# RPi-ILDA_v1.net
KiCad netlist of a schematic drawn in EAGLE
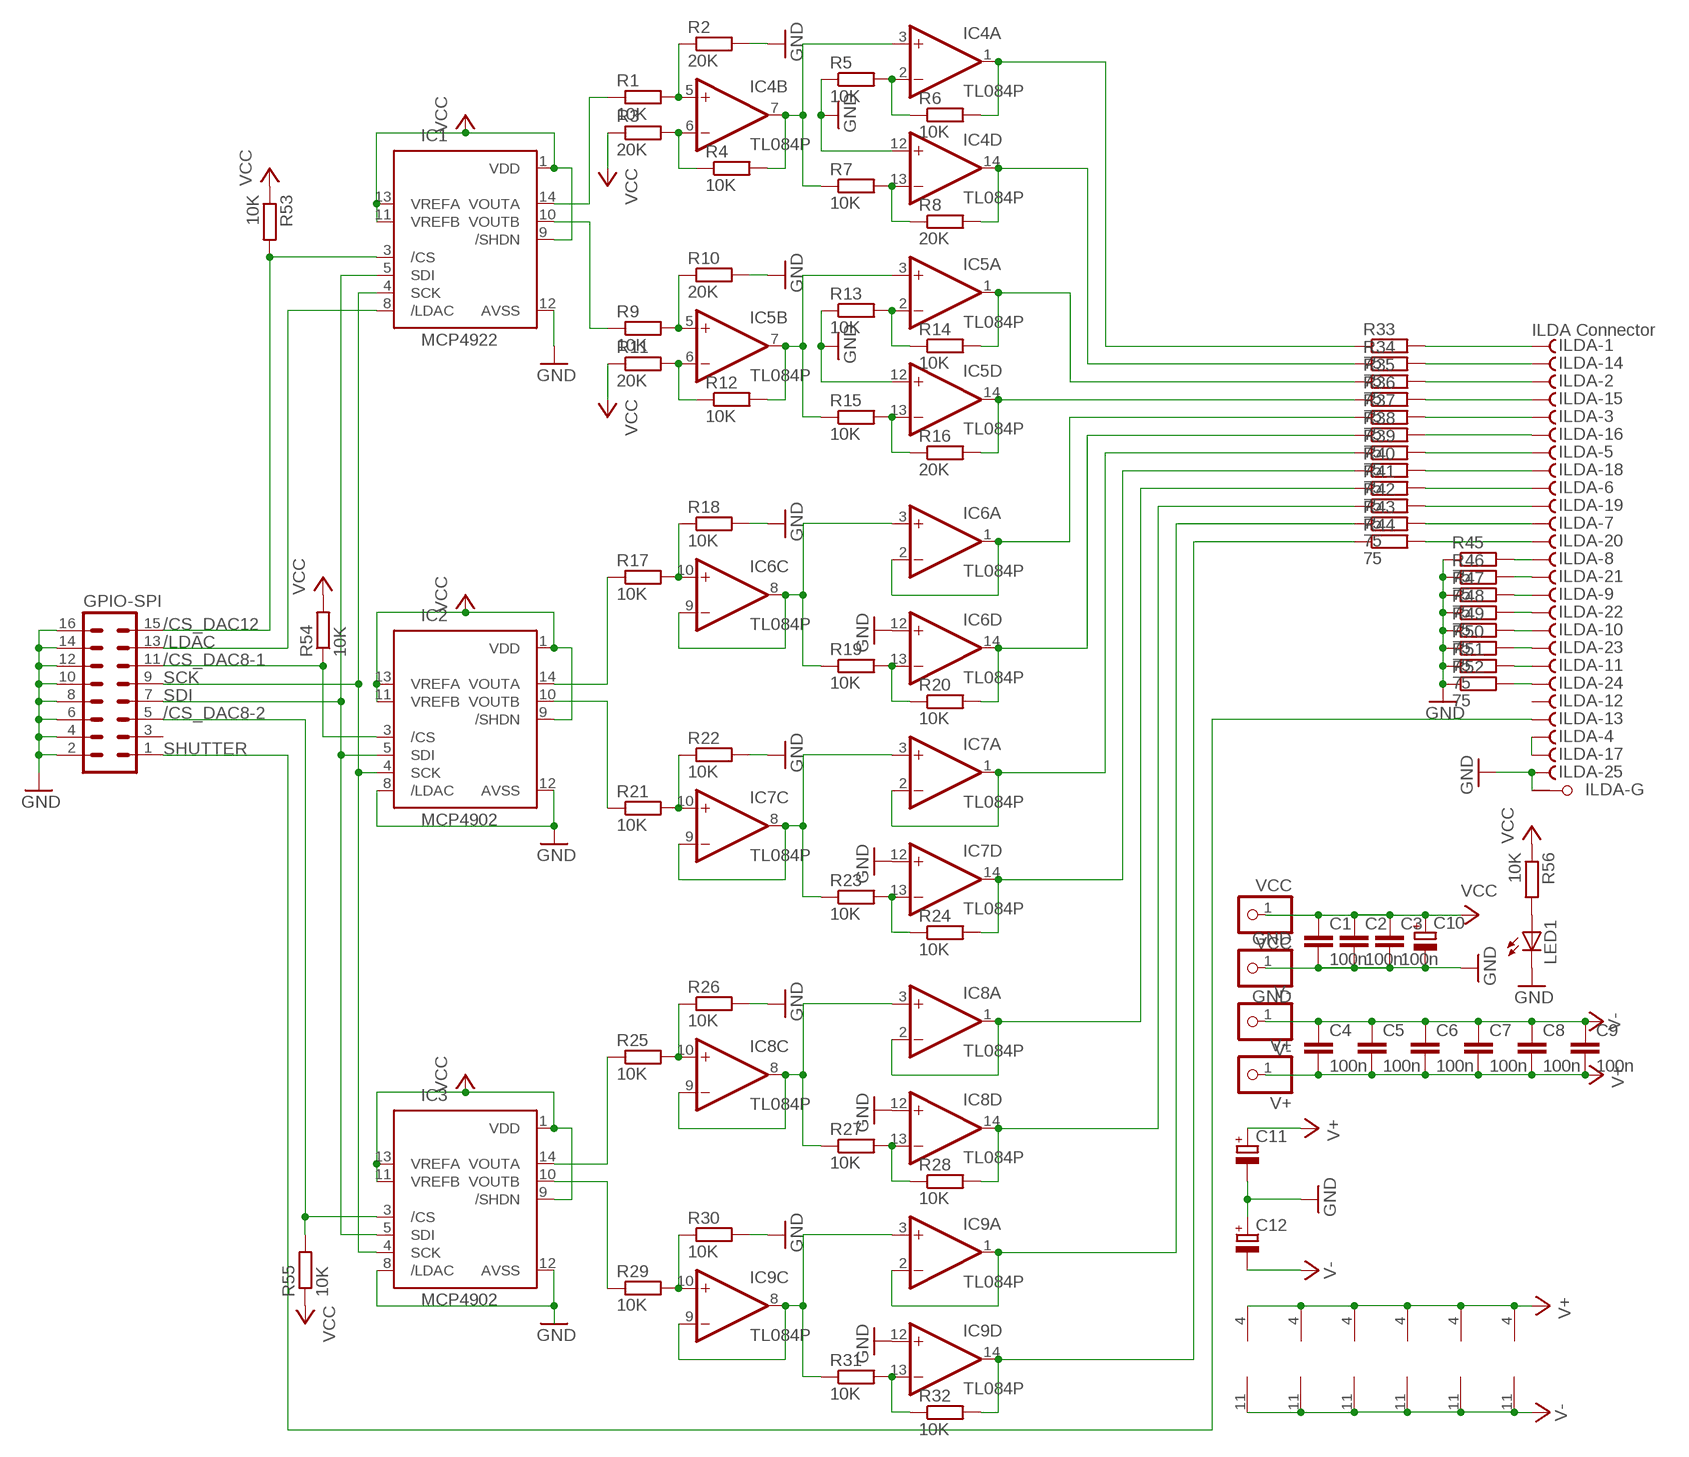
[diagram p0: schematic, sheet 1]

(export (version "E")
  (design (tool "Eeschema 10.0.6"))
  (components
    (comp (ref "C1")
      (value "100n")
      (footprint "eagle-import:C050-024X044")
      (libsource (lib "eagle-import") (part "C-EU050-024X044"))
    )
    (comp (ref "C2")
      (value "100n")
      (footprint "eagle-import:C050-024X044")
      (libsource (lib "eagle-import") (part "C-EU050-024X044"))
    )
    (comp (ref "C3")
      (value "100n")
      (footprint "eagle-import:C050-024X044")
      (libsource (lib "eagle-import") (part "C-EU050-024X044"))
    )
    (comp (ref "C4")
      (value "100n")
      (footprint "eagle-import:C050-024X044")
      (libsource (lib "eagle-import") (part "C-EU050-024X044"))
    )
    (comp (ref "C5")
      (value "100n")
      (footprint "eagle-import:C050-024X044")
      (libsource (lib "eagle-import") (part "C-EU050-024X044"))
    )
    (comp (ref "C6")
      (value "100n")
      (footprint "eagle-import:C050-024X044")
      (libsource (lib "eagle-import") (part "C-EU050-024X044"))
    )
    (comp (ref "C7")
      (value "100n")
      (footprint "eagle-import:C050-024X044")
      (libsource (lib "eagle-import") (part "C-EU050-024X044"))
    )
    (comp (ref "C8")
      (value "100n")
      (footprint "eagle-import:C050-024X044")
      (libsource (lib "eagle-import") (part "C-EU050-024X044"))
    )
    (comp (ref "C9")
      (value "100n")
      (footprint "eagle-import:C050-024X044")
      (libsource (lib "eagle-import") (part "C-EU050-024X044"))
    )
    (comp (ref "C10")
      (value "CPOL-EUE5-6")
      (footprint "eagle-import:E5-6")
      (libsource (lib "eagle-import") (part "CPOL-EUE5-6"))
    )
    (comp (ref "C11")
      (value "CPOL-EUE5-6")
      (footprint "eagle-import:E5-6")
      (libsource (lib "eagle-import") (part "CPOL-EUE5-6"))
    )
    (comp (ref "C12")
      (value "CPOL-EUE5-6")
      (footprint "eagle-import:E5-6")
      (libsource (lib "eagle-import") (part "CPOL-EUE5-6"))
    )
    (comp (ref "GND")
      (value "GND")
      (footprint "eagle-import:1X01")
      (libsource (lib "eagle-import") (part "PINHD-1X1"))
    )
    (comp (ref "GPIO-SPI")
      (value "MA08-2")
      (footprint "eagle-import:MA08-2")
      (libsource (lib "eagle-import") (part "MA08-2"))
    )
    (comp (ref "IC1")
      (value "MCP4922")
      (footprint "eagle-import:DIL14")
      (libsource (lib "eagle-import") (part "MCP4922"))
    )
    (comp (ref "IC2")
      (value "MCP4902")
      (footprint "eagle-import:DIL14")
      (libsource (lib "eagle-import") (part "MCP4922"))
    )
    (comp (ref "IC3")
      (value "MCP4902")
      (footprint "eagle-import:DIL14")
      (libsource (lib "eagle-import") (part "MCP4922"))
    )
    (comp (ref "IC4")
      (value "TL084P")
      (footprint "eagle-import:DIL14")
      (libsource (lib "eagle-import") (part "TL084P"))
    )
    (comp (ref "IC5")
      (value "TL084P")
      (footprint "eagle-import:DIL14")
      (libsource (lib "eagle-import") (part "TL084P"))
    )
    (comp (ref "IC6")
      (value "TL084P")
      (footprint "eagle-import:DIL14")
      (libsource (lib "eagle-import") (part "TL084P"))
    )
    (comp (ref "IC7")
      (value "TL084P")
      (footprint "eagle-import:DIL14")
      (libsource (lib "eagle-import") (part "TL084P"))
    )
    (comp (ref "IC8")
      (value "TL084P")
      (footprint "eagle-import:DIL14")
      (libsource (lib "eagle-import") (part "TL084P"))
    )
    (comp (ref "IC9")
      (value "TL084P")
      (footprint "eagle-import:DIL14")
      (libsource (lib "eagle-import") (part "TL084P"))
    )
    (comp (ref "ILDA")
      (value "ILDA Connector")
      (footprint "eagle-import:F25HP")
      (libsource (lib "eagle-import") (part "F25HPS"))
    )
    (comp (ref "LED1")
      (value "LED3MM")
      (footprint "eagle-import:LED3MM")
      (libsource (lib "eagle-import") (part "LED3MM"))
    )
    (comp (ref "R1")
      (value "10K")
      (footprint "eagle-import:0204_5")
      (libsource (lib "eagle-import") (part "R-EU_0204/5"))
    )
    (comp (ref "R2")
      (value "20K")
      (footprint "eagle-import:0204V")
      (libsource (lib "eagle-import") (part "R-EU_0204/2V"))
    )
    (comp (ref "R3")
      (value "20K")
      (footprint "eagle-import:0204_5")
      (libsource (lib "eagle-import") (part "R-EU_0204/5"))
    )
    (comp (ref "R4")
      (value "10K")
      (footprint "eagle-import:0204V")
      (libsource (lib "eagle-import") (part "R-EU_0204/2V"))
    )
    (comp (ref "R5")
      (value "10K")
      (footprint "eagle-import:0204V")
      (libsource (lib "eagle-import") (part "R-EU_0204/2V"))
    )
    (comp (ref "R6")
      (value "10K")
      (footprint "eagle-import:0204V")
      (libsource (lib "eagle-import") (part "R-EU_0204/2V"))
    )
    (comp (ref "R7")
      (value "10K")
      (footprint "eagle-import:0204_5")
      (libsource (lib "eagle-import") (part "R-EU_0204/5"))
    )
    (comp (ref "R8")
      (value "20K")
      (footprint "eagle-import:0204V")
      (libsource (lib "eagle-import") (part "R-EU_0204/2V"))
    )
    (comp (ref "R9")
      (value "10K")
      (footprint "eagle-import:0204_5")
      (libsource (lib "eagle-import") (part "R-EU_0204/5"))
    )
    (comp (ref "R10")
      (value "20K")
      (footprint "eagle-import:0204V")
      (libsource (lib "eagle-import") (part "R-EU_0204/2V"))
    )
    (comp (ref "R11")
      (value "20K")
      (footprint "eagle-import:0204_5")
      (libsource (lib "eagle-import") (part "R-EU_0204/5"))
    )
    (comp (ref "R12")
      (value "10K")
      (footprint "eagle-import:0204V")
      (libsource (lib "eagle-import") (part "R-EU_0204/2V"))
    )
    (comp (ref "R13")
      (value "10K")
      (footprint "eagle-import:0204V")
      (libsource (lib "eagle-import") (part "R-EU_0204/2V"))
    )
    (comp (ref "R14")
      (value "10K")
      (footprint "eagle-import:0204V")
      (libsource (lib "eagle-import") (part "R-EU_0204/2V"))
    )
    (comp (ref "R15")
      (value "10K")
      (footprint "eagle-import:0204_5")
      (libsource (lib "eagle-import") (part "R-EU_0204/5"))
    )
    (comp (ref "R16")
      (value "20K")
      (footprint "eagle-import:0204V")
      (libsource (lib "eagle-import") (part "R-EU_0204/2V"))
    )
    (comp (ref "R17")
      (value "10K")
      (footprint "eagle-import:0204_5")
      (libsource (lib "eagle-import") (part "R-EU_0204/5"))
    )
    (comp (ref "R18")
      (value "10K")
      (footprint "eagle-import:0204V")
      (libsource (lib "eagle-import") (part "R-EU_0204/2V"))
    )
    (comp (ref "R19")
      (value "10K")
      (footprint "eagle-import:0204V")
      (libsource (lib "eagle-import") (part "R-EU_0204/2V"))
    )
    (comp (ref "R20")
      (value "10K")
      (footprint "eagle-import:0204V")
      (libsource (lib "eagle-import") (part "R-EU_0204/2V"))
    )
    (comp (ref "R21")
      (value "10K")
      (footprint "eagle-import:0204_5")
      (libsource (lib "eagle-import") (part "R-EU_0204/5"))
    )
    (comp (ref "R22")
      (value "10K")
      (footprint "eagle-import:0204_5")
      (libsource (lib "eagle-import") (part "R-EU_0204/5"))
    )
    (comp (ref "R23")
      (value "10K")
      (footprint "eagle-import:0204V")
      (libsource (lib "eagle-import") (part "R-EU_0204/2V"))
    )
    (comp (ref "R24")
      (value "10K")
      (footprint "eagle-import:0204V")
      (libsource (lib "eagle-import") (part "R-EU_0204/2V"))
    )
    (comp (ref "R25")
      (value "10K")
      (footprint "eagle-import:0204_5")
      (libsource (lib "eagle-import") (part "R-EU_0204/5"))
    )
    (comp (ref "R26")
      (value "10K")
      (footprint "eagle-import:0204V")
      (libsource (lib "eagle-import") (part "R-EU_0204/2V"))
    )
    (comp (ref "R27")
      (value "10K")
      (footprint "eagle-import:0204V")
      (libsource (lib "eagle-import") (part "R-EU_0204/2V"))
    )
    (comp (ref "R28")
      (value "10K")
      (footprint "eagle-import:0204V")
      (libsource (lib "eagle-import") (part "R-EU_0204/2V"))
    )
    (comp (ref "R29")
      (value "10K")
      (footprint "eagle-import:0204_5")
      (libsource (lib "eagle-import") (part "R-EU_0204/5"))
    )
    (comp (ref "R30")
      (value "10K")
      (footprint "eagle-import:0204_5")
      (libsource (lib "eagle-import") (part "R-EU_0204/5"))
    )
    (comp (ref "R31")
      (value "10K")
      (footprint "eagle-import:0204V")
      (libsource (lib "eagle-import") (part "R-EU_0204/2V"))
    )
    (comp (ref "R32")
      (value "10K")
      (footprint "eagle-import:0204V")
      (libsource (lib "eagle-import") (part "R-EU_0204/2V"))
    )
    (comp (ref "R33")
      (value "75")
      (footprint "eagle-import:0204V")
      (libsource (lib "eagle-import") (part "R-EU_0204/2V"))
    )
    (comp (ref "R34")
      (value "75")
      (footprint "eagle-import:0204V")
      (libsource (lib "eagle-import") (part "R-EU_0204/2V"))
    )
    (comp (ref "R35")
      (value "75")
      (footprint "eagle-import:0204V")
      (libsource (lib "eagle-import") (part "R-EU_0204/2V"))
    )
    (comp (ref "R36")
      (value "75")
      (footprint "eagle-import:0204V")
      (libsource (lib "eagle-import") (part "R-EU_0204/2V"))
    )
    (comp (ref "R37")
      (value "75")
      (footprint "eagle-import:0204V")
      (libsource (lib "eagle-import") (part "R-EU_0204/2V"))
    )
    (comp (ref "R38")
      (value "75")
      (footprint "eagle-import:0204V")
      (libsource (lib "eagle-import") (part "R-EU_0204/2V"))
    )
    (comp (ref "R39")
      (value "75")
      (footprint "eagle-import:0204V")
      (libsource (lib "eagle-import") (part "R-EU_0204/2V"))
    )
    (comp (ref "R40")
      (value "75")
      (footprint "eagle-import:0204V")
      (libsource (lib "eagle-import") (part "R-EU_0204/2V"))
    )
    (comp (ref "R41")
      (value "75")
      (footprint "eagle-import:0204V")
      (libsource (lib "eagle-import") (part "R-EU_0204/2V"))
    )
    (comp (ref "R42")
      (value "75")
      (footprint "eagle-import:0204V")
      (libsource (lib "eagle-import") (part "R-EU_0204/2V"))
    )
    (comp (ref "R43")
      (value "75")
      (footprint "eagle-import:0204V")
      (libsource (lib "eagle-import") (part "R-EU_0204/2V"))
    )
    (comp (ref "R44")
      (value "75")
      (footprint "eagle-import:0204V")
      (libsource (lib "eagle-import") (part "R-EU_0204/2V"))
    )
    (comp (ref "R45")
      (value "75")
      (footprint "eagle-import:0204V")
      (libsource (lib "eagle-import") (part "R-EU_0204/2V"))
    )
    (comp (ref "R46")
      (value "75")
      (footprint "eagle-import:0204V")
      (libsource (lib "eagle-import") (part "R-EU_0204/2V"))
    )
    (comp (ref "R47")
      (value "75")
      (footprint "eagle-import:0204V")
      (libsource (lib "eagle-import") (part "R-EU_0204/2V"))
    )
    (comp (ref "R48")
      (value "75")
      (footprint "eagle-import:0204V")
      (libsource (lib "eagle-import") (part "R-EU_0204/2V"))
    )
    (comp (ref "R49")
      (value "75")
      (footprint "eagle-import:0204V")
      (libsource (lib "eagle-import") (part "R-EU_0204/2V"))
    )
    (comp (ref "R50")
      (value "75")
      (footprint "eagle-import:0204V")
      (libsource (lib "eagle-import") (part "R-EU_0204/2V"))
    )
    (comp (ref "R51")
      (value "75")
      (footprint "eagle-import:0204V")
      (libsource (lib "eagle-import") (part "R-EU_0204/2V"))
    )
    (comp (ref "R52")
      (value "75")
      (footprint "eagle-import:0204V")
      (libsource (lib "eagle-import") (part "R-EU_0204/2V"))
    )
    (comp (ref "R53")
      (value "10K")
      (footprint "eagle-import:0204_5")
      (libsource (lib "eagle-import") (part "R-EU_0204/5"))
    )
    (comp (ref "R54")
      (value "10K")
      (footprint "eagle-import:0204_5")
      (libsource (lib "eagle-import") (part "R-EU_0204/5"))
    )
    (comp (ref "R55")
      (value "10K")
      (footprint "eagle-import:0204_5")
      (libsource (lib "eagle-import") (part "R-EU_0204/5"))
    )
    (comp (ref "R56")
      (value "10K")
      (footprint "eagle-import:0204V")
      (libsource (lib "eagle-import") (part "R-EU_0204/2V"))
    )
    (comp (ref "V+")
      (value "V+")
      (footprint "eagle-import:1X01")
      (libsource (lib "eagle-import") (part "PINHD-1X1"))
    )
    (comp (ref "V-")
      (value "V-")
      (footprint "eagle-import:1X01")
      (libsource (lib "eagle-import") (part "PINHD-1X1"))
    )
    (comp (ref "VCC")
      (value "VCC")
      (footprint "eagle-import:1X01")
      (libsource (lib "eagle-import") (part "PINHD-1X1"))
    )
  )
  (nets
    (net (code "1") (name "/SCK") (class "Default")
      (node (ref "GPIO-SPI") (pin "9") (pinfunction "9_9") (pintype "passive"))
      (node (ref "IC1") (pin "4") (pinfunction "SCK_4") (pintype "input"))
      (node (ref "IC2") (pin "4") (pinfunction "SCK_4") (pintype "input"))
      (node (ref "IC3") (pin "4") (pinfunction "SCK_4") (pintype "input"))
    )
    (net (code "2") (name "/SDI") (class "Default")
      (node (ref "GPIO-SPI") (pin "7") (pinfunction "7_7") (pintype "passive"))
      (node (ref "IC1") (pin "5") (pinfunction "SDI_5") (pintype "input"))
      (node (ref "IC2") (pin "5") (pinfunction "SDI_5") (pintype "input"))
      (node (ref "IC3") (pin "5") (pinfunction "SDI_5") (pintype "input"))
    )
    (net (code "3") (name "/SHUTTER") (class "Default")
      (node (ref "GPIO-SPI") (pin "1") (pinfunction "1_1") (pintype "passive"))
      (node (ref "ILDA") (pin "13") (pinfunction "F_13") (pintype "passive"))
    )
    (net (code "4") (name "/{slash}CS_DAC8-1") (class "Default")
      (node (ref "GPIO-SPI") (pin "11") (pinfunction "11_11") (pintype "passive"))
      (node (ref "IC2") (pin "3") (pinfunction "/CS_3") (pintype "bidirectional"))
      (node (ref "R54") (pin "1") (pinfunction "1_1") (pintype "passive"))
    )
    (net (code "5") (name "/{slash}CS_DAC8-2") (class "Default")
      (node (ref "GPIO-SPI") (pin "5") (pinfunction "5_5") (pintype "passive"))
      (node (ref "IC3") (pin "3") (pinfunction "/CS_3") (pintype "bidirectional"))
      (node (ref "R55") (pin "2") (pinfunction "2_2") (pintype "passive"))
    )
    (net (code "6") (name "/{slash}CS_DAC12") (class "Default")
      (node (ref "GPIO-SPI") (pin "15") (pinfunction "15_15") (pintype "passive"))
      (node (ref "IC1") (pin "3") (pinfunction "/CS_3") (pintype "bidirectional"))
      (node (ref "R53") (pin "2") (pinfunction "2_2") (pintype "passive"))
    )
    (net (code "7") (name "/{slash}LDAC") (class "Default")
      (node (ref "GPIO-SPI") (pin "13") (pinfunction "13_13") (pintype "passive"))
      (node (ref "IC1") (pin "8") (pinfunction "/LDAC_8") (pintype "input"))
    )
    (net (code "8") (name "GND") (class "Default")
      (node (ref "C1") (pin "2") (pinfunction "2_2") (pintype "passive"))
      (node (ref "C10") (pin "-") (pinfunction "-_-") (pintype "passive"))
      (node (ref "C11") (pin "-") (pinfunction "-_-") (pintype "passive"))
      (node (ref "C12") (pin "+") (pinfunction "+_+") (pintype "passive"))
      (node (ref "C2") (pin "2") (pinfunction "2_2") (pintype "passive"))
      (node (ref "C3") (pin "2") (pinfunction "2_2") (pintype "passive"))
      (node (ref "GND") (pin "1") (pinfunction "1_1") (pintype "passive"))
      (node (ref "GPIO-SPI") (pin "10") (pinfunction "10_10") (pintype "passive"))
      (node (ref "GPIO-SPI") (pin "12") (pinfunction "12_12") (pintype "passive"))
      (node (ref "GPIO-SPI") (pin "14") (pinfunction "14_14") (pintype "passive"))
      (node (ref "GPIO-SPI") (pin "16") (pinfunction "16_16") (pintype "passive"))
      (node (ref "GPIO-SPI") (pin "2") (pinfunction "2_2") (pintype "passive"))
      (node (ref "GPIO-SPI") (pin "4") (pinfunction "4_4") (pintype "passive"))
      (node (ref "GPIO-SPI") (pin "6") (pinfunction "6_6") (pintype "passive"))
      (node (ref "GPIO-SPI") (pin "8") (pinfunction "8_8") (pintype "passive"))
      (node (ref "IC1") (pin "12") (pinfunction "AVSS_12") (pintype "power_in"))
      (node (ref "IC2") (pin "12") (pinfunction "AVSS_12") (pintype "power_in"))
      (node (ref "IC2") (pin "8") (pinfunction "/LDAC_8") (pintype "input"))
      (node (ref "IC3") (pin "12") (pinfunction "AVSS_12") (pintype "power_in"))
      (node (ref "IC3") (pin "8") (pinfunction "/LDAC_8") (pintype "input"))
      (node (ref "IC4") (pin "12") (pinfunction "+IN_12") (pintype "input"))
      (node (ref "IC5") (pin "12") (pinfunction "+IN_12") (pintype "input"))
      (node (ref "IC6") (pin "12") (pinfunction "+IN_12") (pintype "input"))
      (node (ref "IC7") (pin "12") (pinfunction "+IN_12") (pintype "input"))
      (node (ref "IC8") (pin "12") (pinfunction "+IN_12") (pintype "input"))
      (node (ref "IC9") (pin "12") (pinfunction "+IN_12") (pintype "input"))
      (node (ref "ILDA") (pin "25") (pinfunction "F_25") (pintype "passive"))
      (node (ref "ILDA") (pin "G1") (pinfunction "G1_G1") (pintype "passive"))
      (node (ref "LED1") (pin "K") (pinfunction "C_K") (pintype "passive"))
      (node (ref "R10") (pin "2") (pinfunction "2_2") (pintype "passive"))
      (node (ref "R13") (pin "1") (pinfunction "1_1") (pintype "passive"))
      (node (ref "R18") (pin "2") (pinfunction "2_2") (pintype "passive"))
      (node (ref "R2") (pin "2") (pinfunction "2_2") (pintype "passive"))
      (node (ref "R22") (pin "2") (pinfunction "2_2") (pintype "passive"))
      (node (ref "R26") (pin "2") (pinfunction "2_2") (pintype "passive"))
      (node (ref "R30") (pin "2") (pinfunction "2_2") (pintype "passive"))
      (node (ref "R45") (pin "1") (pinfunction "1_1") (pintype "passive"))
      (node (ref "R46") (pin "1") (pinfunction "1_1") (pintype "passive"))
      (node (ref "R47") (pin "1") (pinfunction "1_1") (pintype "passive"))
      (node (ref "R48") (pin "1") (pinfunction "1_1") (pintype "passive"))
      (node (ref "R49") (pin "1") (pinfunction "1_1") (pintype "passive"))
      (node (ref "R5") (pin "1") (pinfunction "1_1") (pintype "passive"))
      (node (ref "R50") (pin "1") (pinfunction "1_1") (pintype "passive"))
      (node (ref "R51") (pin "1") (pinfunction "1_1") (pintype "passive"))
      (node (ref "R52") (pin "1") (pinfunction "1_1") (pintype "passive"))
    )
    (net (code "9") (name "Net-(IC1-VOUTA)") (class "Default")
      (node (ref "IC1") (pin "14") (pinfunction "VOUTA_14") (pintype "output"))
      (node (ref "R1") (pin "1") (pinfunction "1_1") (pintype "passive"))
    )
    (net (code "10") (name "Net-(IC1-VOUTB)") (class "Default")
      (node (ref "IC1") (pin "10") (pinfunction "VOUTB_10") (pintype "output"))
      (node (ref "R9") (pin "1") (pinfunction "1_1") (pintype "passive"))
    )
    (net (code "11") (name "Net-(IC2-VOUTA)") (class "Default")
      (node (ref "IC2") (pin "14") (pinfunction "VOUTA_14") (pintype "output"))
      (node (ref "R17") (pin "1") (pinfunction "1_1") (pintype "passive"))
    )
    (net (code "12") (name "Net-(IC2-VOUTB)") (class "Default")
      (node (ref "IC2") (pin "10") (pinfunction "VOUTB_10") (pintype "output"))
      (node (ref "R21") (pin "1") (pinfunction "1_1") (pintype "passive"))
    )
    (net (code "13") (name "Net-(IC3-VOUTA)") (class "Default")
      (node (ref "IC3") (pin "14") (pinfunction "VOUTA_14") (pintype "output"))
      (node (ref "R25") (pin "1") (pinfunction "1_1") (pintype "passive"))
    )
    (net (code "14") (name "Net-(IC3-VOUTB)") (class "Default")
      (node (ref "IC3") (pin "10") (pinfunction "VOUTB_10") (pintype "output"))
      (node (ref "R29") (pin "1") (pinfunction "1_1") (pintype "passive"))
    )
    (net (code "15") (name "Net-(IC4A-+IN)") (class "Default")
      (node (ref "IC4") (pin "3") (pinfunction "+IN_3") (pintype "input"))
      (node (ref "IC4") (pin "7") (pinfunction "OUT_7") (pintype "output"))
      (node (ref "R4") (pin "2") (pinfunction "2_2") (pintype "passive"))
      (node (ref "R7") (pin "1") (pinfunction "1_1") (pintype "passive"))
    )
    (net (code "16") (name "Net-(IC4A--IN)") (class "Default")
      (node (ref "IC4") (pin "2") (pinfunction "-IN_2") (pintype "input"))
      (node (ref "R5") (pin "2") (pinfunction "2_2") (pintype "passive"))
      (node (ref "R6") (pin "1") (pinfunction "1_1") (pintype "passive"))
    )
    (net (code "17") (name "Net-(IC4A-OUT)") (class "Default")
      (node (ref "IC4") (pin "1") (pinfunction "OUT_1") (pintype "output"))
      (node (ref "R33") (pin "1") (pinfunction "1_1") (pintype "passive"))
      (node (ref "R6") (pin "2") (pinfunction "2_2") (pintype "passive"))
    )
    (net (code "18") (name "Net-(IC4B-+IN)") (class "Default")
      (node (ref "IC4") (pin "5") (pinfunction "+IN_5") (pintype "input"))
      (node (ref "R1") (pin "2") (pinfunction "2_2") (pintype "passive"))
      (node (ref "R2") (pin "1") (pinfunction "1_1") (pintype "passive"))
    )
    (net (code "19") (name "Net-(IC4B--IN)") (class "Default")
      (node (ref "IC4") (pin "6") (pinfunction "-IN_6") (pintype "input"))
      (node (ref "R3") (pin "2") (pinfunction "2_2") (pintype "passive"))
      (node (ref "R4") (pin "1") (pinfunction "1_1") (pintype "passive"))
    )
    (net (code "20") (name "Net-(IC4D--IN)") (class "Default")
      (node (ref "IC4") (pin "13") (pinfunction "-IN_13") (pintype "input"))
      (node (ref "R7") (pin "2") (pinfunction "2_2") (pintype "passive"))
      (node (ref "R8") (pin "1") (pinfunction "1_1") (pintype "passive"))
    )
    (net (code "21") (name "Net-(IC4D-OUT)") (class "Default")
      (node (ref "IC4") (pin "14") (pinfunction "OUT_14") (pintype "output"))
      (node (ref "R34") (pin "1") (pinfunction "1_1") (pintype "passive"))
      (node (ref "R8") (pin "2") (pinfunction "2_2") (pintype "passive"))
    )
    (net (code "22") (name "Net-(IC5A-+IN)") (class "Default")
      (node (ref "IC5") (pin "3") (pinfunction "+IN_3") (pintype "input"))
      (node (ref "IC5") (pin "7") (pinfunction "OUT_7") (pintype "output"))
      (node (ref "R12") (pin "2") (pinfunction "2_2") (pintype "passive"))
      (node (ref "R15") (pin "1") (pinfunction "1_1") (pintype "passive"))
    )
    (net (code "23") (name "Net-(IC5A--IN)") (class "Default")
      (node (ref "IC5") (pin "2") (pinfunction "-IN_2") (pintype "input"))
      (node (ref "R13") (pin "2") (pinfunction "2_2") (pintype "passive"))
      (node (ref "R14") (pin "1") (pinfunction "1_1") (pintype "passive"))
    )
    (net (code "24") (name "Net-(IC5A-OUT)") (class "Default")
      (node (ref "IC5") (pin "1") (pinfunction "OUT_1") (pintype "output"))
      (node (ref "R14") (pin "2") (pinfunction "2_2") (pintype "passive"))
      (node (ref "R35") (pin "1") (pinfunction "1_1") (pintype "passive"))
    )
    (net (code "25") (name "Net-(IC5B-+IN)") (class "Default")
      (node (ref "IC5") (pin "5") (pinfunction "+IN_5") (pintype "input"))
      (node (ref "R10") (pin "1") (pinfunction "1_1") (pintype "passive"))
      (node (ref "R9") (pin "2") (pinfunction "2_2") (pintype "passive"))
    )
    (net (code "26") (name "Net-(IC5B--IN)") (class "Default")
      (node (ref "IC5") (pin "6") (pinfunction "-IN_6") (pintype "input"))
      (node (ref "R11") (pin "2") (pinfunction "2_2") (pintype "passive"))
      (node (ref "R12") (pin "1") (pinfunction "1_1") (pintype "passive"))
    )
    (net (code "27") (name "Net-(IC5D--IN)") (class "Default")
      (node (ref "IC5") (pin "13") (pinfunction "-IN_13") (pintype "input"))
      (node (ref "R15") (pin "2") (pinfunction "2_2") (pintype "passive"))
      (node (ref "R16") (pin "1") (pinfunction "1_1") (pintype "passive"))
    )
    (net (code "28") (name "Net-(IC5D-OUT)") (class "Default")
      (node (ref "IC5") (pin "14") (pinfunction "OUT_14") (pintype "output"))
      (node (ref "R16") (pin "2") (pinfunction "2_2") (pintype "passive"))
      (node (ref "R36") (pin "1") (pinfunction "1_1") (pintype "passive"))
    )
    (net (code "29") (name "Net-(IC6A-+IN)") (class "Default")
      (node (ref "IC6") (pin "3") (pinfunction "+IN_3") (pintype "input"))
      (node (ref "IC6") (pin "8") (pinfunction "OUT_8") (pintype "output"))
      (node (ref "IC6") (pin "9") (pinfunction "-IN_9") (pintype "input"))
      (node (ref "R19") (pin "1") (pinfunction "1_1") (pintype "passive"))
    )
    (net (code "30") (name "Net-(IC6A--IN)") (class "Default")
      (node (ref "IC6") (pin "1") (pinfunction "OUT_1") (pintype "output"))
      (node (ref "IC6") (pin "2") (pinfunction "-IN_2") (pintype "input"))
      (node (ref "R37") (pin "1") (pinfunction "1_1") (pintype "passive"))
    )
    (net (code "31") (name "Net-(IC6C-+IN)") (class "Default")
      (node (ref "IC6") (pin "10") (pinfunction "+IN_10") (pintype "input"))
      (node (ref "R17") (pin "2") (pinfunction "2_2") (pintype "passive"))
      (node (ref "R18") (pin "1") (pinfunction "1_1") (pintype "passive"))
    )
    (net (code "32") (name "Net-(IC6D--IN)") (class "Default")
      (node (ref "IC6") (pin "13") (pinfunction "-IN_13") (pintype "input"))
      (node (ref "R19") (pin "2") (pinfunction "2_2") (pintype "passive"))
      (node (ref "R20") (pin "1") (pinfunction "1_1") (pintype "passive"))
    )
    (net (code "33") (name "Net-(IC6D-OUT)") (class "Default")
      (node (ref "IC6") (pin "14") (pinfunction "OUT_14") (pintype "output"))
      (node (ref "R20") (pin "2") (pinfunction "2_2") (pintype "passive"))
      (node (ref "R38") (pin "1") (pinfunction "1_1") (pintype "passive"))
    )
    (net (code "34") (name "Net-(IC7A-+IN)") (class "Default")
      (node (ref "IC7") (pin "3") (pinfunction "+IN_3") (pintype "input"))
      (node (ref "IC7") (pin "8") (pinfunction "OUT_8") (pintype "output"))
      (node (ref "IC7") (pin "9") (pinfunction "-IN_9") (pintype "input"))
      (node (ref "R23") (pin "1") (pinfunction "1_1") (pintype "passive"))
    )
    (net (code "35") (name "Net-(IC7A--IN)") (class "Default")
      (node (ref "IC7") (pin "1") (pinfunction "OUT_1") (pintype "output"))
      (node (ref "IC7") (pin "2") (pinfunction "-IN_2") (pintype "input"))
      (node (ref "R39") (pin "1") (pinfunction "1_1") (pintype "passive"))
    )
    (net (code "36") (name "Net-(IC7C-+IN)") (class "Default")
      (node (ref "IC7") (pin "10") (pinfunction "+IN_10") (pintype "input"))
      (node (ref "R21") (pin "2") (pinfunction "2_2") (pintype "passive"))
      (node (ref "R22") (pin "1") (pinfunction "1_1") (pintype "passive"))
    )
    (net (code "37") (name "Net-(IC7D--IN)") (class "Default")
      (node (ref "IC7") (pin "13") (pinfunction "-IN_13") (pintype "input"))
      (node (ref "R23") (pin "2") (pinfunction "2_2") (pintype "passive"))
      (node (ref "R24") (pin "1") (pinfunction "1_1") (pintype "passive"))
    )
    (net (code "38") (name "Net-(IC7D-OUT)") (class "Default")
      (node (ref "IC7") (pin "14") (pinfunction "OUT_14") (pintype "output"))
      (node (ref "R24") (pin "2") (pinfunction "2_2") (pintype "passive"))
      (node (ref "R40") (pin "1") (pinfunction "1_1") (pintype "passive"))
    )
    (net (code "39") (name "Net-(IC8A-+IN)") (class "Default")
      (node (ref "IC8") (pin "3") (pinfunction "+IN_3") (pintype "input"))
      (node (ref "IC8") (pin "8") (pinfunction "OUT_8") (pintype "output"))
      (node (ref "IC8") (pin "9") (pinfunction "-IN_9") (pintype "input"))
      (node (ref "R27") (pin "1") (pinfunction "1_1") (pintype "passive"))
    )
    (net (code "40") (name "Net-(IC8A--IN)") (class "Default")
      (node (ref "IC8") (pin "1") (pinfunction "OUT_1") (pintype "output"))
      (node (ref "IC8") (pin "2") (pinfunction "-IN_2") (pintype "input"))
      (node (ref "R41") (pin "1") (pinfunction "1_1") (pintype "passive"))
    )
    (net (code "41") (name "Net-(IC8C-+IN)") (class "Default")
      (node (ref "IC8") (pin "10") (pinfunction "+IN_10") (pintype "input"))
      (node (ref "R25") (pin "2") (pinfunction "2_2") (pintype "passive"))
      (node (ref "R26") (pin "1") (pinfunction "1_1") (pintype "passive"))
    )
    (net (code "42") (name "Net-(IC8D--IN)") (class "Default")
      (node (ref "IC8") (pin "13") (pinfunction "-IN_13") (pintype "input"))
      (node (ref "R27") (pin "2") (pinfunction "2_2") (pintype "passive"))
      (node (ref "R28") (pin "1") (pinfunction "1_1") (pintype "passive"))
    )
    (net (code "43") (name "Net-(IC8D-OUT)") (class "Default")
      (node (ref "IC8") (pin "14") (pinfunction "OUT_14") (pintype "output"))
      (node (ref "R28") (pin "2") (pinfunction "2_2") (pintype "passive"))
      (node (ref "R42") (pin "1") (pinfunction "1_1") (pintype "passive"))
    )
    (net (code "44") (name "Net-(IC9A-+IN)") (class "Default")
      (node (ref "IC9") (pin "3") (pinfunction "+IN_3") (pintype "input"))
      (node (ref "IC9") (pin "8") (pinfunction "OUT_8") (pintype "output"))
      (node (ref "IC9") (pin "9") (pinfunction "-IN_9") (pintype "input"))
      (node (ref "R31") (pin "1") (pinfunction "1_1") (pintype "passive"))
    )
    (net (code "45") (name "Net-(IC9A--IN)") (class "Default")
      (node (ref "IC9") (pin "1") (pinfunction "OUT_1") (pintype "output"))
      (node (ref "IC9") (pin "2") (pinfunction "-IN_2") (pintype "input"))
      (node (ref "R43") (pin "1") (pinfunction "1_1") (pintype "passive"))
    )
    (net (code "46") (name "Net-(IC9C-+IN)") (class "Default")
      (node (ref "IC9") (pin "10") (pinfunction "+IN_10") (pintype "input"))
      (node (ref "R29") (pin "2") (pinfunction "2_2") (pintype "passive"))
      (node (ref "R30") (pin "1") (pinfunction "1_1") (pintype "passive"))
    )
    (net (code "47") (name "Net-(IC9D--IN)") (class "Default")
      (node (ref "IC9") (pin "13") (pinfunction "-IN_13") (pintype "input"))
      (node (ref "R31") (pin "2") (pinfunction "2_2") (pintype "passive"))
      (node (ref "R32") (pin "1") (pinfunction "1_1") (pintype "passive"))
    )
    (net (code "48") (name "Net-(IC9D-OUT)") (class "Default")
      (node (ref "IC9") (pin "14") (pinfunction "OUT_14") (pintype "output"))
      (node (ref "R32") (pin "2") (pinfunction "2_2") (pintype "passive"))
      (node (ref "R44") (pin "1") (pinfunction "1_1") (pintype "passive"))
    )
    (net (code "49") (name "Net-(ILDAA-F)") (class "Default")
      (node (ref "ILDA") (pin "1") (pinfunction "F_1") (pintype "passive"))
      (node (ref "R33") (pin "2") (pinfunction "2_2") (pintype "passive"))
    )
    (net (code "50") (name "Net-(ILDAB-F)") (class "Default")
      (node (ref "ILDA") (pin "10") (pinfunction "F_10") (pintype "passive"))
      (node (ref "R49") (pin "2") (pinfunction "2_2") (pintype "passive"))
    )
    (net (code "51") (name "Net-(ILDAC-F)") (class "Default")
      (node (ref "ILDA") (pin "11") (pinfunction "F_11") (pintype "passive"))
      (node (ref "R51") (pin "2") (pinfunction "2_2") (pintype "passive"))
    )
    (net (code "52") (name "Net-(ILDAF-F)") (class "Default")
      (node (ref "ILDA") (pin "14") (pinfunction "F_14") (pintype "passive"))
      (node (ref "R34") (pin "2") (pinfunction "2_2") (pintype "passive"))
    )
    (net (code "53") (name "Net-(ILDAG-F)") (class "Default")
      (node (ref "ILDA") (pin "15") (pinfunction "F_15") (pintype "passive"))
      (node (ref "R36") (pin "2") (pinfunction "2_2") (pintype "passive"))
    )
    (net (code "54") (name "Net-(ILDAH-F)") (class "Default")
      (node (ref "ILDA") (pin "16") (pinfunction "F_16") (pintype "passive"))
      (node (ref "R38") (pin "2") (pinfunction "2_2") (pintype "passive"))
    )
    (net (code "55") (name "Net-(ILDAI-F)") (class "Default")
      (node (ref "ILDA") (pin "17") (pinfunction "F_17") (pintype "passive"))
      (node (ref "ILDA") (pin "4") (pinfunction "F_4") (pintype "passive"))
    )
    (net (code "56") (name "Net-(ILDAJ-F)") (class "Default")
      (node (ref "ILDA") (pin "18") (pinfunction "F_18") (pintype "passive"))
      (node (ref "R40") (pin "2") (pinfunction "2_2") (pintype "passive"))
    )
    (net (code "57") (name "Net-(ILDAK-F)") (class "Default")
      (node (ref "ILDA") (pin "19") (pinfunction "F_19") (pintype "passive"))
      (node (ref "R42") (pin "2") (pinfunction "2_2") (pintype "passive"))
    )
    (net (code "58") (name "Net-(ILDAL-F)") (class "Default")
      (node (ref "ILDA") (pin "2") (pinfunction "F_2") (pintype "passive"))
      (node (ref "R35") (pin "2") (pinfunction "2_2") (pintype "passive"))
    )
    (net (code "59") (name "Net-(ILDAM-F)") (class "Default")
      (node (ref "ILDA") (pin "20") (pinfunction "F_20") (pintype "passive"))
      (node (ref "R44") (pin "2") (pinfunction "2_2") (pintype "passive"))
    )
    (net (code "60") (name "Net-(ILDAN-F)") (class "Default")
      (node (ref "ILDA") (pin "21") (pinfunction "F_21") (pintype "passive"))
      (node (ref "R46") (pin "2") (pinfunction "2_2") (pintype "passive"))
    )
    (net (code "61") (name "Net-(ILDAO-F)") (class "Default")
      (node (ref "ILDA") (pin "22") (pinfunction "F_22") (pintype "passive"))
      (node (ref "R48") (pin "2") (pinfunction "2_2") (pintype "passive"))
    )
    (net (code "62") (name "Net-(ILDAP-F)") (class "Default")
      (node (ref "ILDA") (pin "23") (pinfunction "F_23") (pintype "passive"))
      (node (ref "R50") (pin "2") (pinfunction "2_2") (pintype "passive"))
    )
    (net (code "63") (name "Net-(ILDAQ-F)") (class "Default")
      (node (ref "ILDA") (pin "24") (pinfunction "F_24") (pintype "passive"))
      (node (ref "R52") (pin "2") (pinfunction "2_2") (pintype "passive"))
    )
    (net (code "64") (name "Net-(ILDAS-F)") (class "Default")
      (node (ref "ILDA") (pin "3") (pinfunction "F_3") (pintype "passive"))
      (node (ref "R37") (pin "2") (pinfunction "2_2") (pintype "passive"))
    )
    (net (code "65") (name "Net-(ILDAU-F)") (class "Default")
      (node (ref "ILDA") (pin "5") (pinfunction "F_5") (pintype "passive"))
      (node (ref "R39") (pin "2") (pinfunction "2_2") (pintype "passive"))
    )
    (net (code "66") (name "Net-(ILDAV-F)") (class "Default")
      (node (ref "ILDA") (pin "6") (pinfunction "F_6") (pintype "passive"))
      (node (ref "R41") (pin "2") (pinfunction "2_2") (pintype "passive"))
    )
    (net (code "67") (name "Net-(ILDAW-F)") (class "Default")
      (node (ref "ILDA") (pin "7") (pinfunction "F_7") (pintype "passive"))
      (node (ref "R43") (pin "2") (pinfunction "2_2") (pintype "passive"))
    )
    (net (code "68") (name "Net-(ILDAX-F)") (class "Default")
      (node (ref "ILDA") (pin "8") (pinfunction "F_8") (pintype "passive"))
      (node (ref "R45") (pin "2") (pinfunction "2_2") (pintype "passive"))
    )
    (net (code "69") (name "Net-(ILDAY-F)") (class "Default")
      (node (ref "ILDA") (pin "9") (pinfunction "F_9") (pintype "passive"))
      (node (ref "R47") (pin "2") (pinfunction "2_2") (pintype "passive"))
    )
    (net (code "70") (name "Net-(LED1-PadA)") (class "Default")
      (node (ref "LED1") (pin "A") (pinfunction "A_A") (pintype "passive"))
      (node (ref "R56") (pin "2") (pinfunction "2_2") (pintype "passive"))
    )
    (net (code "71") (name "V+") (class "Default")
      (node (ref "C11") (pin "+") (pinfunction "+_+") (pintype "passive"))
      (node (ref "C4") (pin "2") (pinfunction "2_2") (pintype "passive"))
      (node (ref "C5") (pin "2") (pinfunction "2_2") (pintype "passive"))
      (node (ref "C6") (pin "2") (pinfunction "2_2") (pintype "passive"))
      (node (ref "C7") (pin "2") (pinfunction "2_2") (pintype "passive"))
      (node (ref "C8") (pin "2") (pinfunction "2_2") (pintype "passive"))
      (node (ref "C9") (pin "2") (pinfunction "2_2") (pintype "passive"))
      (node (ref "IC4") (pin "4") (pinfunction "V+_4") (pintype "power_in"))
      (node (ref "IC5") (pin "4") (pinfunction "V+_4") (pintype "power_in"))
      (node (ref "IC6") (pin "4") (pinfunction "V+_4") (pintype "power_in"))
      (node (ref "IC7") (pin "4") (pinfunction "V+_4") (pintype "power_in"))
      (node (ref "IC8") (pin "4") (pinfunction "V+_4") (pintype "power_in"))
      (node (ref "IC9") (pin "4") (pinfunction "V+_4") (pintype "power_in"))
      (node (ref "V+") (pin "1") (pinfunction "1_1") (pintype "passive"))
    )
    (net (code "72") (name "V-") (class "Default")
      (node (ref "C12") (pin "-") (pinfunction "-_-") (pintype "passive"))
      (node (ref "C4") (pin "1") (pinfunction "1_1") (pintype "passive"))
      (node (ref "C5") (pin "1") (pinfunction "1_1") (pintype "passive"))
      (node (ref "C6") (pin "1") (pinfunction "1_1") (pintype "passive"))
      (node (ref "C7") (pin "1") (pinfunction "1_1") (pintype "passive"))
      (node (ref "C8") (pin "1") (pinfunction "1_1") (pintype "passive"))
      (node (ref "C9") (pin "1") (pinfunction "1_1") (pintype "passive"))
      (node (ref "IC4") (pin "11") (pinfunction "V-_11") (pintype "power_in"))
      (node (ref "IC5") (pin "11") (pinfunction "V-_11") (pintype "power_in"))
      (node (ref "IC6") (pin "11") (pinfunction "V-_11") (pintype "power_in"))
      (node (ref "IC7") (pin "11") (pinfunction "V-_11") (pintype "power_in"))
      (node (ref "IC8") (pin "11") (pinfunction "V-_11") (pintype "power_in"))
      (node (ref "IC9") (pin "11") (pinfunction "V-_11") (pintype "power_in"))
      (node (ref "V-") (pin "1") (pinfunction "1_1") (pintype "passive"))
    )
    (net (code "73") (name "VCC") (class "Default")
      (node (ref "C1") (pin "1") (pinfunction "1_1") (pintype "passive"))
      (node (ref "C10") (pin "+") (pinfunction "+_+") (pintype "passive"))
      (node (ref "C2") (pin "1") (pinfunction "1_1") (pintype "passive"))
      (node (ref "C3") (pin "1") (pinfunction "1_1") (pintype "passive"))
      (node (ref "IC1") (pin "1") (pinfunction "VDD_1") (pintype "power_in"))
      (node (ref "IC1") (pin "11") (pinfunction "VREFB_11") (pintype "bidirectional"))
      (node (ref "IC1") (pin "13") (pinfunction "VREFA_13") (pintype "input"))
      (node (ref "IC1") (pin "9") (pinfunction "/SHDN_9") (pintype "input"))
      (node (ref "IC2") (pin "1") (pinfunction "VDD_1") (pintype "power_in"))
      (node (ref "IC2") (pin "11") (pinfunction "VREFB_11") (pintype "bidirectional"))
      (node (ref "IC2") (pin "13") (pinfunction "VREFA_13") (pintype "input"))
      (node (ref "IC2") (pin "9") (pinfunction "/SHDN_9") (pintype "input"))
      (node (ref "IC3") (pin "1") (pinfunction "VDD_1") (pintype "power_in"))
      (node (ref "IC3") (pin "11") (pinfunction "VREFB_11") (pintype "bidirectional"))
      (node (ref "IC3") (pin "13") (pinfunction "VREFA_13") (pintype "input"))
      (node (ref "IC3") (pin "9") (pinfunction "/SHDN_9") (pintype "input"))
      (node (ref "R11") (pin "1") (pinfunction "1_1") (pintype "passive"))
      (node (ref "R3") (pin "1") (pinfunction "1_1") (pintype "passive"))
      (node (ref "R53") (pin "1") (pinfunction "1_1") (pintype "passive"))
      (node (ref "R54") (pin "2") (pinfunction "2_2") (pintype "passive"))
      (node (ref "R55") (pin "1") (pinfunction "1_1") (pintype "passive"))
      (node (ref "R56") (pin "1") (pinfunction "1_1") (pintype "passive"))
      (node (ref "VCC") (pin "1") (pinfunction "1_1") (pintype "passive"))
    )
    (net (code "74") (name "unconnected-(GPIO-SPI-Pad3)") (class "Default")
      (node (ref "GPIO-SPI") (pin "3") (pinfunction "3_3") (pintype "passive"))
    )
    (net (code "75") (name "unconnected-(ILDA-PadG2)") (class "Default")
      (node (ref "ILDA") (pin "G2") (pinfunction "G2_G2") (pintype "passive"))
    )
    (net (code "76") (name "unconnected-(ILDAD-F-Pad12)") (class "Default")
      (node (ref "ILDA") (pin "12") (pinfunction "F_12") (pintype "passive"))
    )
  )
)
